# DFPlayer.net
KiCad netlist of a schematic drawn in EAGLE
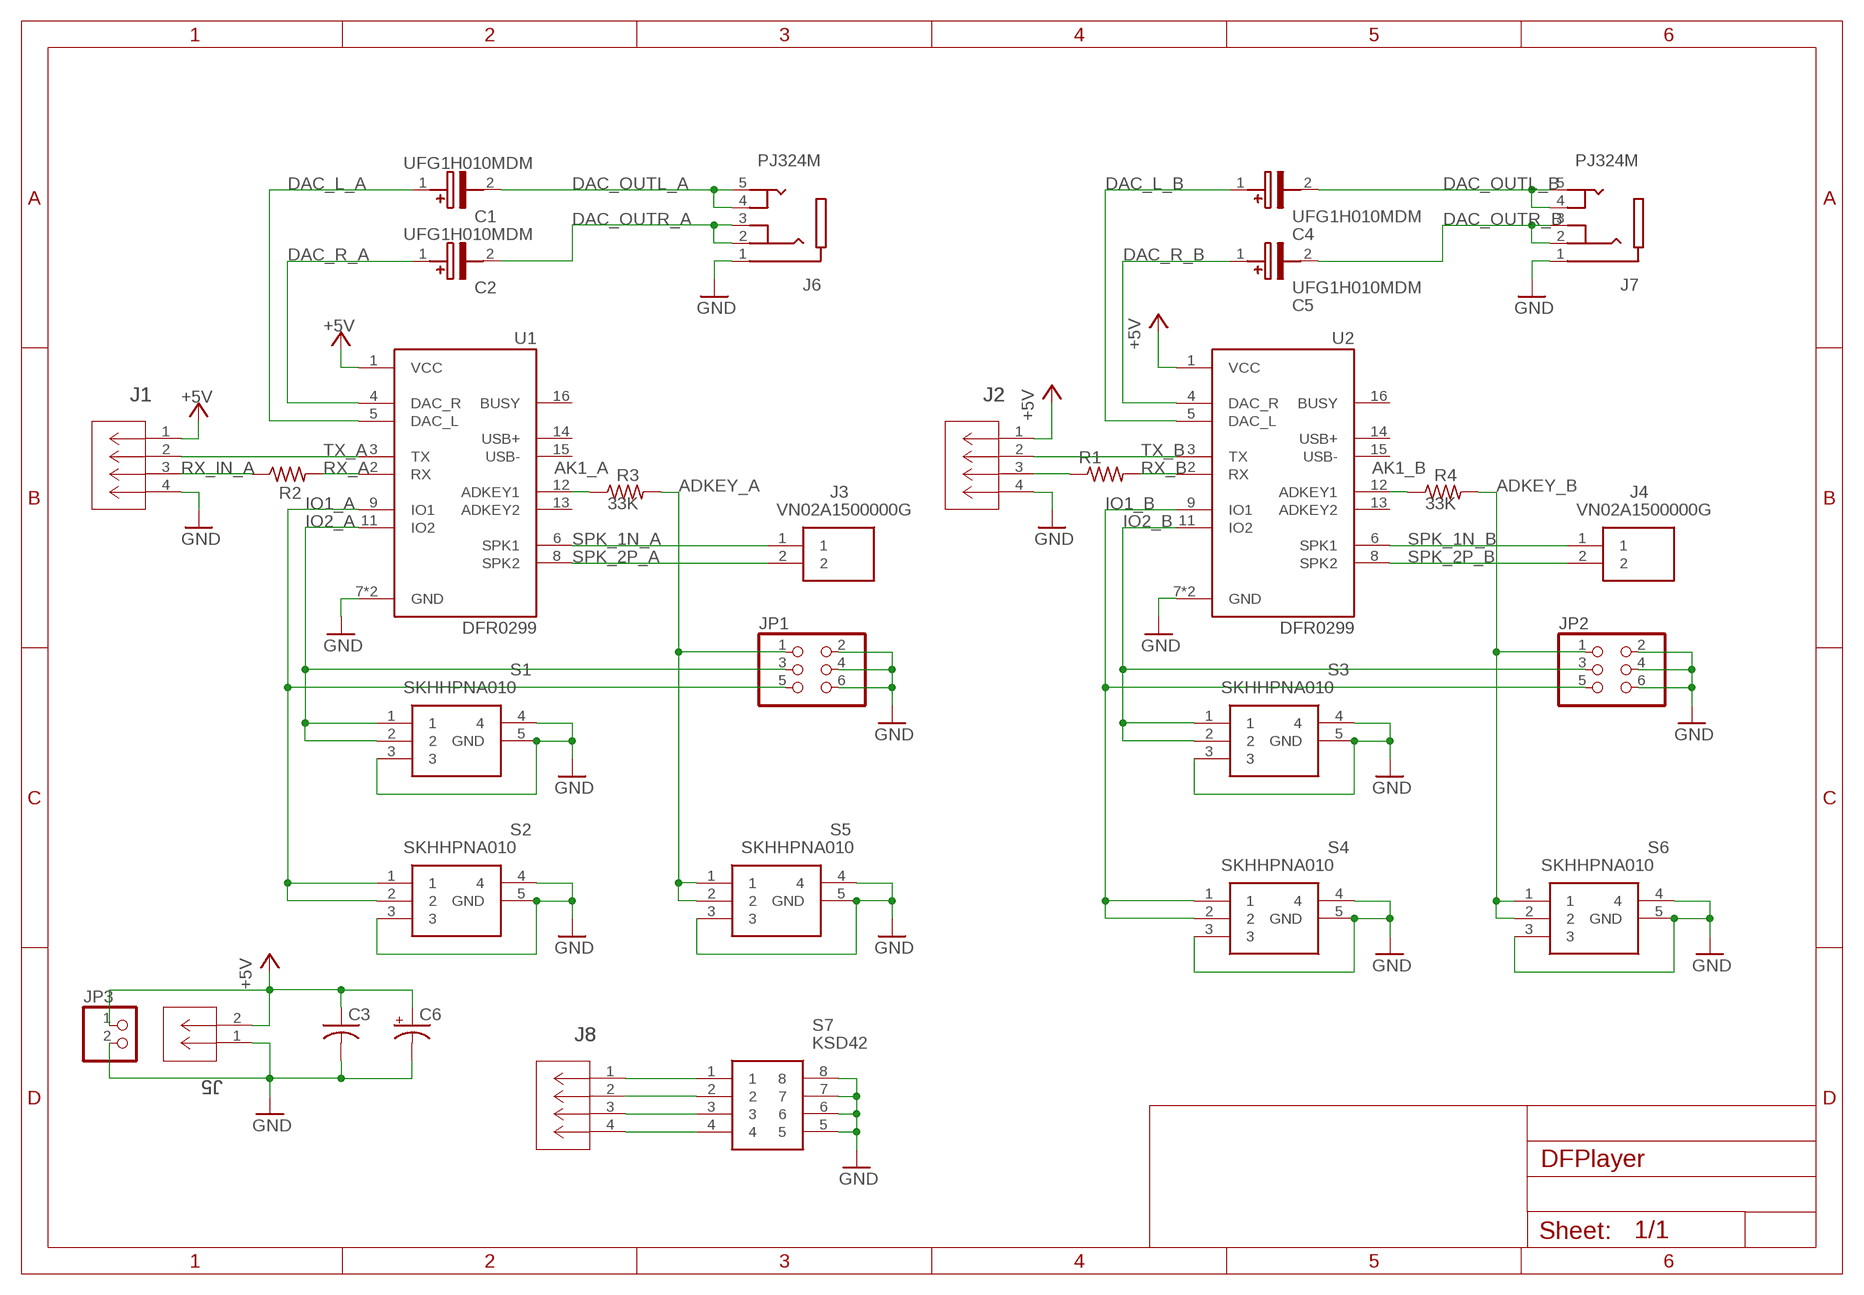
[diagram p0: schematic, sheet 1]

(export (version "E")
  (design (tool "Eeschema 10.0.6"))
  (components
    (comp (ref "C1")
      (value "UFG1H010MDM")
      (footprint "eagle-import:CAPPRD200W60D550H1250")
      (fields (field (name "MOUSER_PART_NUMBER") "647-UFG1H010MDM"))
      (libsource (lib "eagle-import") (part "UFG1H010MDM"))
    )
    (comp (ref "C2")
      (value "UFG1H010MDM")
      (footprint "eagle-import:CAPPRD200W60D550H1250")
      (fields (field (name "MOUSER_PART_NUMBER") "647-UFG1H010MDM"))
      (libsource (lib "eagle-import") (part "UFG1H010MDM"))
    )
    (comp (ref "C3")
      (value "C-US025-024X044")
      (footprint "eagle-import:C025-024X044")
      (libsource (lib "eagle-import") (part "C-US025-024X044"))
    )
    (comp (ref "C4")
      (value "UFG1H010MDM")
      (footprint "eagle-import:CAPPRD200W60D550H1250")
      (fields (field (name "MOUSER_PART_NUMBER") "647-UFG1H010MDM"))
      (libsource (lib "eagle-import") (part "UFG1H010MDM"))
    )
    (comp (ref "C5")
      (value "UFG1H010MDM")
      (footprint "eagle-import:CAPPRD200W60D550H1250")
      (fields (field (name "MOUSER_PART_NUMBER") "647-UFG1H010MDM"))
      (libsource (lib "eagle-import") (part "UFG1H010MDM"))
    )
    (comp (ref "C6")
      (value "CPOL-USB45181A")
      (footprint "eagle-import:B45181A")
      (libsource (lib "eagle-import") (part "CPOL-USB45181A"))
    )
    (comp (ref "J1")
      (value "S4B-PH-K-S(LF)(SN)")
      (footprint "eagle-import:CONN_S4B-PH-K-S_JST")
      (fields (field (name "COPYRIGHT") "Copyright (C) 2024 Ultra Librarian. All rights reserved."))
      (libsource (lib "eagle-import") (part "S4B-PH-K-S(LF)(SN)"))
    )
    (comp (ref "J2")
      (value "S4B-PH-K-S(LF)(SN)")
      (footprint "eagle-import:CONN_S4B-PH-K-S_JST")
      (fields (field (name "COPYRIGHT") "Copyright (C) 2024 Ultra Librarian. All rights reserved."))
      (libsource (lib "eagle-import") (part "S4B-PH-K-S(LF)(SN)"))
    )
    (comp (ref "J3")
      (value "VN02A1500000G")
      (footprint "eagle-import:VN02A1500000G")
      (fields (field (name "MOUSER_PART_NUMBER") "649-VN02A15000J0G"))
      (libsource (lib "eagle-import") (part "VN02A1500000G"))
    )
    (comp (ref "J4")
      (value "VN02A1500000G")
      (footprint "eagle-import:VN02A1500000G")
      (fields (field (name "MOUSER_PART_NUMBER") "649-VN02A15000J0G"))
      (libsource (lib "eagle-import") (part "VN02A1500000G"))
    )
    (comp (ref "J5")
      (value "S2B-PH-K-S(LF)(SN)")
      (footprint "eagle-import:CONN_S2B-PH-K-S_JST")
      (fields (field (name "COPYRIGHT") "Copyright (C) 2024 Ultra Librarian. All rights reserved."))
      (libsource (lib "eagle-import") (part "S2B-PH-K-S(LF)(SN)"))
    )
    (comp (ref "J6")
      (value "PJ324M")
      (footprint "eagle-import:WENZHOU_PJ324M")
      (fields (field (name "MF") "Wenzhou QingPu Electronics Co.Ltd"))
      (libsource (lib "eagle-import") (part "PJ324M"))
    )
    (comp (ref "J7")
      (value "PJ324M")
      (footprint "eagle-import:WENZHOU_PJ324M")
      (fields (field (name "MF") "Wenzhou QingPu Electronics Co.Ltd"))
      (libsource (lib "eagle-import") (part "PJ324M"))
    )
    (comp (ref "J8")
      (value "S4B-PH-K-S(LF)(SN)")
      (footprint "eagle-import:CONN_S4B-PH-K-S_JST")
      (fields (field (name "COPYRIGHT") "Copyright (C) 2024 Ultra Librarian. All rights reserved."))
      (libsource (lib "eagle-import") (part "S4B-PH-K-S(LF)(SN)"))
    )
    (comp (ref "JP1")
      (value "PINHD-2X3")
      (footprint "eagle-import:2X03")
      (libsource (lib "eagle-import") (part "PINHD-2X3"))
    )
    (comp (ref "JP2")
      (value "PINHD-2X3")
      (footprint "eagle-import:2X03")
      (libsource (lib "eagle-import") (part "PINHD-2X3"))
    )
    (comp (ref "JP3")
      (value "PINHD-1X2")
      (footprint "eagle-import:1X02")
      (libsource (lib "eagle-import") (part "PINHD-1X2"))
    )
    (comp (ref "R1")
      (value "R-US_0204/7")
      (footprint "eagle-import:0204_7")
      (libsource (lib "eagle-import") (part "R-US_0204/7"))
    )
    (comp (ref "R2")
      (value "R-US_0204/7")
      (footprint "eagle-import:0204_7")
      (libsource (lib "eagle-import") (part "R-US_0204/7"))
    )
    (comp (ref "R3")
      (value "R-US_0204/7")
      (footprint "eagle-import:0204_7")
      (fields (field (name "POPULARITY") "48") (field (name "POPULARITY_1") "33K"))
      (libsource (lib "eagle-import") (part "R-US_0204/7"))
    )
    (comp (ref "R4")
      (value "R-US_0204/7")
      (footprint "eagle-import:0204_7")
      (fields (field (name "POPULARITY") "48") (field (name "POPULARITY_1") "33K"))
      (libsource (lib "eagle-import") (part "R-US_0204/7"))
    )
    (comp (ref "S1")
      (value "SKHHPNA010")
      (footprint "eagle-import:SKHHPJA010")
      (fields (field (name "MOUSER_PART_NUMBER") "688-SKHHPN"))
      (libsource (lib "eagle-import") (part "SKHHPNA010"))
    )
    (comp (ref "S2")
      (value "SKHHPNA010")
      (footprint "eagle-import:SKHHPJA010")
      (fields (field (name "MOUSER_PART_NUMBER") "688-SKHHPN"))
      (libsource (lib "eagle-import") (part "SKHHPNA010"))
    )
    (comp (ref "S3")
      (value "SKHHPNA010")
      (footprint "eagle-import:SKHHPJA010")
      (fields (field (name "MOUSER_PART_NUMBER") "688-SKHHPN"))
      (libsource (lib "eagle-import") (part "SKHHPNA010"))
    )
    (comp (ref "S4")
      (value "SKHHPNA010")
      (footprint "eagle-import:SKHHPJA010")
      (fields (field (name "MOUSER_PART_NUMBER") "688-SKHHPN"))
      (libsource (lib "eagle-import") (part "SKHHPNA010"))
    )
    (comp (ref "S5")
      (value "SKHHPNA010")
      (footprint "eagle-import:SKHHPJA010")
      (fields (field (name "MOUSER_PART_NUMBER") "688-SKHHPN"))
      (libsource (lib "eagle-import") (part "SKHHPNA010"))
    )
    (comp (ref "S6")
      (value "SKHHPNA010")
      (footprint "eagle-import:SKHHPJA010")
      (fields (field (name "MOUSER_PART_NUMBER") "688-SKHHPN"))
      (libsource (lib "eagle-import") (part "SKHHPNA010"))
    )
    (comp (ref "S7")
      (value "KSD42")
      (footprint "eagle-import:DIP815W60P254L1210H450Q8N")
      (libsource (lib "eagle-import") (part "KSD42"))
    )
    (comp (ref "U1")
      (value "DFR0299")
      (footprint "eagle-import:MODULE_DFR0299")
      (fields (field (name "MF") "DFRobot"))
      (libsource (lib "eagle-import") (part "DFR0299"))
    )
    (comp (ref "U2")
      (value "DFR0299")
      (footprint "eagle-import:MODULE_DFR0299")
      (fields (field (name "MF") "DFRobot"))
      (libsource (lib "eagle-import") (part "DFR0299"))
    )
  )
  (nets
    (net (code "1") (name "+5V") (class "Default")
      (node (ref "C3") (pin "1") (pinfunction "1_1") (pintype "passive"))
      (node (ref "C6") (pin "+") (pinfunction "+_+") (pintype "passive"))
      (node (ref "J1") (pin "1") (pinfunction "1_1") (pintype "passive"))
      (node (ref "J2") (pin "1") (pinfunction "1_1") (pintype "passive"))
      (node (ref "J5") (pin "2") (pinfunction "2_2") (pintype "passive"))
      (node (ref "JP3") (pin "1") (pinfunction "1_1") (pintype "passive"))
      (node (ref "U1") (pin "1") (pinfunction "VCC_1") (pintype "power_in"))
      (node (ref "U2") (pin "1") (pinfunction "VCC_1") (pintype "power_in"))
    )
    (net (code "2") (name "/ADKEY_A") (class "Default")
      (node (ref "JP1") (pin "1") (pinfunction "1_1") (pintype "passive"))
      (node (ref "R3") (pin "2") (pinfunction "2_2") (pintype "passive"))
      (node (ref "S5") (pin "1") (pinfunction "1_1") (pintype "bidirectional"))
      (node (ref "S5") (pin "2") (pinfunction "2_2") (pintype "bidirectional"))
    )
    (net (code "3") (name "/ADKEY_B") (class "Default")
      (node (ref "JP2") (pin "1") (pinfunction "1_1") (pintype "passive"))
      (node (ref "R4") (pin "2") (pinfunction "2_2") (pintype "passive"))
      (node (ref "S6") (pin "1") (pinfunction "1_1") (pintype "bidirectional"))
      (node (ref "S6") (pin "2") (pinfunction "2_2") (pintype "bidirectional"))
    )
    (net (code "4") (name "/AK1_A") (class "Default")
      (node (ref "R3") (pin "1") (pinfunction "1_1") (pintype "passive"))
      (node (ref "U1") (pin "12") (pinfunction "ADKEY1_12") (pintype "input"))
    )
    (net (code "5") (name "/AK1_B") (class "Default")
      (node (ref "R4") (pin "1") (pinfunction "1_1") (pintype "passive"))
      (node (ref "U2") (pin "12") (pinfunction "ADKEY1_12") (pintype "input"))
    )
    (net (code "6") (name "/DAC_L_A") (class "Default")
      (node (ref "C1") (pin "1") (pinfunction "+_1") (pintype "bidirectional"))
      (node (ref "U1") (pin "5") (pinfunction "DAC_L_5") (pintype "output"))
    )
    (net (code "7") (name "/DAC_L_B") (class "Default")
      (node (ref "C4") (pin "1") (pinfunction "+_1") (pintype "bidirectional"))
      (node (ref "U2") (pin "5") (pinfunction "DAC_L_5") (pintype "output"))
    )
    (net (code "8") (name "/DAC_OUTL_A") (class "Default")
      (node (ref "C1") (pin "2") (pinfunction "-_2") (pintype "bidirectional"))
      (node (ref "J6") (pin "4") (pinfunction "TIP_1_4") (pintype "passive"))
      (node (ref "J6") (pin "5") (pinfunction "TIP_2_5") (pintype "passive"))
    )
    (net (code "9") (name "/DAC_OUTL_B") (class "Default")
      (node (ref "C4") (pin "2") (pinfunction "-_2") (pintype "bidirectional"))
      (node (ref "J7") (pin "4") (pinfunction "TIP_1_4") (pintype "passive"))
      (node (ref "J7") (pin "5") (pinfunction "TIP_2_5") (pintype "passive"))
    )
    (net (code "10") (name "/DAC_OUTR_A") (class "Default")
      (node (ref "C2") (pin "2") (pinfunction "-_2") (pintype "bidirectional"))
      (node (ref "J6") (pin "2") (pinfunction "RING_1_2") (pintype "passive"))
      (node (ref "J6") (pin "3") (pinfunction "RING_2_3") (pintype "passive"))
    )
    (net (code "11") (name "/DAC_OUTR_B") (class "Default")
      (node (ref "C5") (pin "2") (pinfunction "-_2") (pintype "bidirectional"))
      (node (ref "J7") (pin "2") (pinfunction "RING_1_2") (pintype "passive"))
      (node (ref "J7") (pin "3") (pinfunction "RING_2_3") (pintype "passive"))
    )
    (net (code "12") (name "/DAC_R_A") (class "Default")
      (node (ref "C2") (pin "1") (pinfunction "+_1") (pintype "bidirectional"))
      (node (ref "U1") (pin "4") (pinfunction "DAC_R_4") (pintype "output"))
    )
    (net (code "13") (name "/DAC_R_B") (class "Default")
      (node (ref "C5") (pin "1") (pinfunction "+_1") (pintype "bidirectional"))
      (node (ref "U2") (pin "4") (pinfunction "DAC_R_4") (pintype "output"))
    )
    (net (code "14") (name "/IO1_A") (class "Default")
      (node (ref "JP1") (pin "5") (pinfunction "5_5") (pintype "passive"))
      (node (ref "S2") (pin "1") (pinfunction "1_1") (pintype "bidirectional"))
      (node (ref "S2") (pin "2") (pinfunction "2_2") (pintype "bidirectional"))
      (node (ref "U1") (pin "9") (pinfunction "IO1_9") (pintype "bidirectional"))
    )
    (net (code "15") (name "/IO1_B") (class "Default")
      (node (ref "JP2") (pin "5") (pinfunction "5_5") (pintype "passive"))
      (node (ref "S4") (pin "1") (pinfunction "1_1") (pintype "bidirectional"))
      (node (ref "S4") (pin "2") (pinfunction "2_2") (pintype "bidirectional"))
      (node (ref "U2") (pin "9") (pinfunction "IO1_9") (pintype "bidirectional"))
    )
    (net (code "16") (name "/IO2_A") (class "Default")
      (node (ref "JP1") (pin "3") (pinfunction "3_3") (pintype "passive"))
      (node (ref "S1") (pin "1") (pinfunction "1_1") (pintype "bidirectional"))
      (node (ref "S1") (pin "2") (pinfunction "2_2") (pintype "bidirectional"))
      (node (ref "U1") (pin "11") (pinfunction "IO2_11") (pintype "bidirectional"))
    )
    (net (code "17") (name "/IO2_B") (class "Default")
      (node (ref "JP2") (pin "3") (pinfunction "3_3") (pintype "passive"))
      (node (ref "S3") (pin "1") (pinfunction "1_1") (pintype "bidirectional"))
      (node (ref "S3") (pin "2") (pinfunction "2_2") (pintype "bidirectional"))
      (node (ref "U2") (pin "11") (pinfunction "IO2_11") (pintype "bidirectional"))
    )
    (net (code "18") (name "/RX_A") (class "Default")
      (node (ref "R2") (pin "2") (pinfunction "2_2") (pintype "passive"))
      (node (ref "U1") (pin "2") (pinfunction "RX_2") (pintype "input"))
    )
    (net (code "19") (name "/RX_B") (class "Default")
      (node (ref "R1") (pin "2") (pinfunction "2_2") (pintype "passive"))
      (node (ref "U2") (pin "2") (pinfunction "RX_2") (pintype "input"))
    )
    (net (code "20") (name "/RX_IN_A") (class "Default")
      (node (ref "J1") (pin "3") (pinfunction "3_3") (pintype "passive"))
      (node (ref "R2") (pin "1") (pinfunction "1_1") (pintype "passive"))
    )
    (net (code "21") (name "/SPK_1N_A") (class "Default")
      (node (ref "J3") (pin "1") (pinfunction "1_1") (pintype "bidirectional"))
      (node (ref "U1") (pin "6") (pinfunction "SPK1_6") (pintype "passive"))
    )
    (net (code "22") (name "/SPK_1N_B") (class "Default")
      (node (ref "J4") (pin "1") (pinfunction "1_1") (pintype "bidirectional"))
      (node (ref "U2") (pin "6") (pinfunction "SPK1_6") (pintype "passive"))
    )
    (net (code "23") (name "/SPK_2P_A") (class "Default")
      (node (ref "J3") (pin "2") (pinfunction "2_2") (pintype "bidirectional"))
      (node (ref "U1") (pin "8") (pinfunction "SPK2_8") (pintype "passive"))
    )
    (net (code "24") (name "/SPK_2P_B") (class "Default")
      (node (ref "J4") (pin "2") (pinfunction "2_2") (pintype "bidirectional"))
      (node (ref "U2") (pin "8") (pinfunction "SPK2_8") (pintype "passive"))
    )
    (net (code "25") (name "/TX_A") (class "Default")
      (node (ref "J1") (pin "2") (pinfunction "2_2") (pintype "passive"))
      (node (ref "U1") (pin "3") (pinfunction "TX_3") (pintype "output"))
    )
    (net (code "26") (name "/TX_B") (class "Default")
      (node (ref "J2") (pin "2") (pinfunction "2_2") (pintype "passive"))
      (node (ref "U2") (pin "3") (pinfunction "TX_3") (pintype "output"))
    )
    (net (code "27") (name "GND") (class "Default")
      (node (ref "C3") (pin "2") (pinfunction "2_2") (pintype "passive"))
      (node (ref "C6") (pin "-") (pinfunction "-_-") (pintype "passive"))
      (node (ref "J1") (pin "4") (pinfunction "4_4") (pintype "passive"))
      (node (ref "J2") (pin "4") (pinfunction "4_4") (pintype "passive"))
      (node (ref "J5") (pin "1") (pinfunction "1_1") (pintype "passive"))
      (node (ref "J6") (pin "1") (pinfunction "SLEEVE_1") (pintype "passive"))
      (node (ref "J7") (pin "1") (pinfunction "SLEEVE_1") (pintype "passive"))
      (node (ref "JP1") (pin "2") (pinfunction "2_2") (pintype "passive"))
      (node (ref "JP1") (pin "4") (pinfunction "4_4") (pintype "passive"))
      (node (ref "JP1") (pin "6") (pinfunction "6_6") (pintype "passive"))
      (node (ref "JP2") (pin "2") (pinfunction "2_2") (pintype "passive"))
      (node (ref "JP2") (pin "4") (pinfunction "4_4") (pintype "passive"))
      (node (ref "JP2") (pin "6") (pinfunction "6_6") (pintype "passive"))
      (node (ref "JP3") (pin "2") (pinfunction "2_2") (pintype "passive"))
      (node (ref "S1") (pin "3") (pinfunction "3_3") (pintype "bidirectional"))
      (node (ref "S1") (pin "4") (pinfunction "4_4") (pintype "bidirectional"))
      (node (ref "S1") (pin "5") (pinfunction "GND_5") (pintype "bidirectional"))
      (node (ref "S2") (pin "3") (pinfunction "3_3") (pintype "bidirectional"))
      (node (ref "S2") (pin "4") (pinfunction "4_4") (pintype "bidirectional"))
      (node (ref "S2") (pin "5") (pinfunction "GND_5") (pintype "bidirectional"))
      (node (ref "S3") (pin "3") (pinfunction "3_3") (pintype "bidirectional"))
      (node (ref "S3") (pin "4") (pinfunction "4_4") (pintype "bidirectional"))
      (node (ref "S3") (pin "5") (pinfunction "GND_5") (pintype "bidirectional"))
      (node (ref "S4") (pin "3") (pinfunction "3_3") (pintype "bidirectional"))
      (node (ref "S4") (pin "4") (pinfunction "4_4") (pintype "bidirectional"))
      (node (ref "S4") (pin "5") (pinfunction "GND_5") (pintype "bidirectional"))
      (node (ref "S5") (pin "3") (pinfunction "3_3") (pintype "bidirectional"))
      (node (ref "S5") (pin "4") (pinfunction "4_4") (pintype "bidirectional"))
      (node (ref "S5") (pin "5") (pinfunction "GND_5") (pintype "bidirectional"))
      (node (ref "S6") (pin "3") (pinfunction "3_3") (pintype "bidirectional"))
      (node (ref "S6") (pin "4") (pinfunction "4_4") (pintype "bidirectional"))
      (node (ref "S6") (pin "5") (pinfunction "GND_5") (pintype "bidirectional"))
      (node (ref "S7") (pin "5") (pinfunction "5_5") (pintype "bidirectional"))
      (node (ref "S7") (pin "6") (pinfunction "6_6") (pintype "bidirectional"))
      (node (ref "S7") (pin "7") (pinfunction "7_7") (pintype "bidirectional"))
      (node (ref "S7") (pin "8") (pinfunction "8_8") (pintype "bidirectional"))
      (node (ref "U1") (pin "10") (pinfunction "GND_10") (pintype "power_in"))
      (node (ref "U1") (pin "7") (pinfunction "GND_7") (pintype "power_in"))
      (node (ref "U2") (pin "10") (pinfunction "GND_10") (pintype "power_in"))
      (node (ref "U2") (pin "7") (pinfunction "GND_7") (pintype "power_in"))
    )
    (net (code "28") (name "Net-(J2-Pad3)") (class "Default")
      (node (ref "J2") (pin "3") (pinfunction "3_3") (pintype "passive"))
      (node (ref "R1") (pin "1") (pinfunction "1_1") (pintype "passive"))
    )
    (net (code "29") (name "Net-(J8-Pad1)") (class "Default")
      (node (ref "J8") (pin "1") (pinfunction "1_1") (pintype "passive"))
      (node (ref "S7") (pin "1") (pinfunction "1_1") (pintype "bidirectional"))
    )
    (net (code "30") (name "Net-(J8-Pad2)") (class "Default")
      (node (ref "J8") (pin "2") (pinfunction "2_2") (pintype "passive"))
      (node (ref "S7") (pin "2") (pinfunction "2_2") (pintype "bidirectional"))
    )
    (net (code "31") (name "Net-(J8-Pad3)") (class "Default")
      (node (ref "J8") (pin "3") (pinfunction "3_3") (pintype "passive"))
      (node (ref "S7") (pin "3") (pinfunction "3_3") (pintype "bidirectional"))
    )
    (net (code "32") (name "Net-(J8-Pad4)") (class "Default")
      (node (ref "J8") (pin "4") (pinfunction "4_4") (pintype "passive"))
      (node (ref "S7") (pin "4") (pinfunction "4_4") (pintype "bidirectional"))
    )
    (net (code "33") (name "unconnected-(U1-ADKEY2-Pad13)") (class "Default")
      (node (ref "U1") (pin "13") (pinfunction "ADKEY2_13") (pintype "input"))
    )
    (net (code "34") (name "unconnected-(U1-BUSY-Pad16)") (class "Default")
      (node (ref "U1") (pin "16") (pinfunction "BUSY_16") (pintype "input"))
    )
    (net (code "35") (name "unconnected-(U1-USB+-Pad14)") (class "Default")
      (node (ref "U1") (pin "14") (pinfunction "USB+_14") (pintype "input"))
    )
    (net (code "36") (name "unconnected-(U1-USB--Pad15)") (class "Default")
      (node (ref "U1") (pin "15") (pinfunction "USB-_15") (pintype "input"))
    )
    (net (code "37") (name "unconnected-(U2-ADKEY2-Pad13)") (class "Default")
      (node (ref "U2") (pin "13") (pinfunction "ADKEY2_13") (pintype "input"))
    )
    (net (code "38") (name "unconnected-(U2-BUSY-Pad16)") (class "Default")
      (node (ref "U2") (pin "16") (pinfunction "BUSY_16") (pintype "input"))
    )
    (net (code "39") (name "unconnected-(U2-USB+-Pad14)") (class "Default")
      (node (ref "U2") (pin "14") (pinfunction "USB+_14") (pintype "input"))
    )
    (net (code "40") (name "unconnected-(U2-USB--Pad15)") (class "Default")
      (node (ref "U2") (pin "15") (pinfunction "USB-_15") (pintype "input"))
    )
  )
)
